# Link.net
KiCad netlist of a schematic drawn in EasyEDA Pro
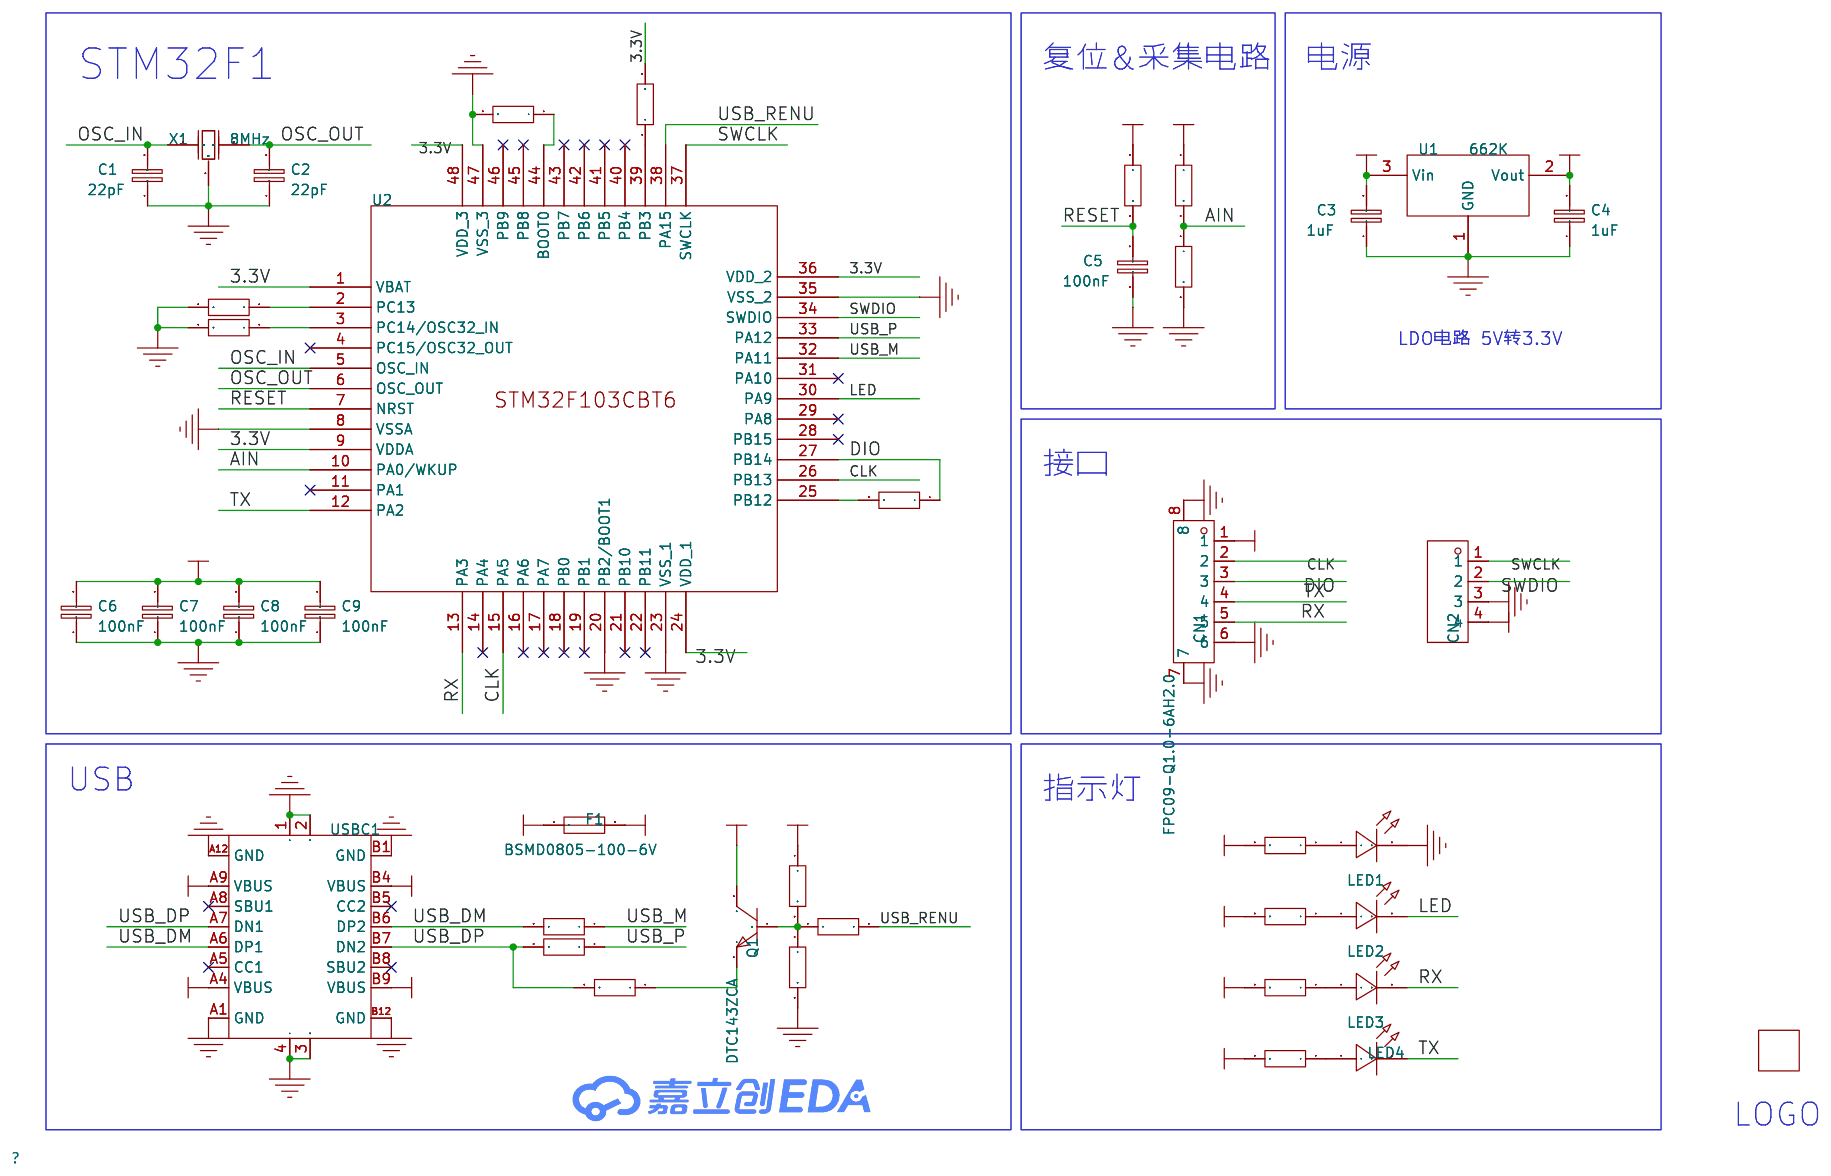
[diagram p0: schematic sheet]

(export (version "E")
  (design (tool "Eeschema 10.0.6"))
  (components
    (comp (ref "C1")
      (value "22pF")
      (fields
        (field (name "Manufacturer Part") "CL10C220JB8NNNC")
        (field (name "Manufacturer") "SAMSUNG(三星)")
      )
      (libsource (lib "easyedapro") (part "C0603"))
    )
    (comp (ref "C2")
      (value "22pF")
      (fields
        (field (name "Manufacturer Part") "CL10C220JB8NNNC")
        (field (name "Manufacturer") "SAMSUNG(三星)")
      )
      (libsource (lib "easyedapro") (part "C0603"))
    )
    (comp (ref "C3")
      (value "1uF")
      (fields
        (field (name "Manufacturer Part") "CL10A106KP8NNNC")
        (field (name "Manufacturer") "SAMSUNG(三星)")
      )
      (libsource (lib "easyedapro") (part "C0603"))
    )
    (comp (ref "C4")
      (value "1uF")
      (fields
        (field (name "Manufacturer Part") "CL10A106KP8NNNC")
        (field (name "Manufacturer") "SAMSUNG(三星)")
      )
      (libsource (lib "easyedapro") (part "C0603"))
    )
    (comp (ref "C5")
      (value "100nF")
      (fields
        (field (name "Manufacturer Part") "CC0603KRX7R9BB104")
        (field (name "Manufacturer") "YAGEO(国巨)")
      )
      (libsource (lib "easyedapro") (part "C0603"))
    )
    (comp (ref "C6")
      (value "100nF")
      (fields
        (field (name "Manufacturer Part") "CL10A106KP8NNNC")
        (field (name "Manufacturer") "SAMSUNG(三星)")
      )
      (libsource (lib "easyedapro") (part "C0603"))
    )
    (comp (ref "C7")
      (value "100nF")
      (fields
        (field (name "Manufacturer Part") "CL10A106KP8NNNC")
        (field (name "Manufacturer") "SAMSUNG(三星)")
      )
      (libsource (lib "easyedapro") (part "C0603"))
    )
    (comp (ref "C8")
      (value "100nF")
      (fields
        (field (name "Manufacturer Part") "CL10A106KP8NNNC")
        (field (name "Manufacturer") "SAMSUNG(三星)")
      )
      (libsource (lib "easyedapro") (part "C0603"))
    )
    (comp (ref "C9")
      (value "100nF")
      (fields
        (field (name "Manufacturer Part") "CL10A106KP8NNNC")
        (field (name "Manufacturer") "SAMSUNG(三星)")
      )
      (libsource (lib "easyedapro") (part "C0603"))
    )
    (comp (ref "CN1")
      (value "FPC09-Q1.0-6AH2.0")
      (fields (field (name "Manufacturer") "XYECONN(辛译)"))
      (libsource (lib "easyedapro") (part "WAFER-SH1.0-6PWB"))
    )
    (comp (ref "CN2")
      (value "X6511WRS-04H-C60D48")
      (footprint "easyedapro:HDR-SMD_4P-P2.54-H-M-W13.3-N")
      (fields (field (name "Manufacturer") "XKB Connection(中国星坤)"))
      (libsource (lib "easyedapro") (part "X6511WRS-04H- C60D48"))
    )
    (comp (ref "F1")
      (value "BSMD0805-100-6V")
      (fields (field (name "Manufacturer") "BHFUSE(佰宏)"))
      (libsource (lib "easyedapro") (part "F1206"))
    )
    (comp (ref "H1")
      (value "MoonGrt")
      (footprint "easyedapro:MoonGrt")
      (libsource (lib "easyedapro") (part "MoonGrt"))
    )
    (comp (ref "LED1")
      (value "LTST-C193TBKT-5A")
      (fields (field (name "Manufacturer") "LITEON(光宝)"))
      (libsource (lib "easyedapro") (part "LED0603B"))
    )
    (comp (ref "LED2")
      (value "LTST-C193TBKT-5A")
      (fields (field (name "Manufacturer") "LITEON(光宝)"))
      (libsource (lib "easyedapro") (part "LED0603B"))
    )
    (comp (ref "LED3")
      (value "LTST-C193TBKT-5A")
      (fields (field (name "Manufacturer") "LITEON(光宝)"))
      (libsource (lib "easyedapro") (part "LED0603B"))
    )
    (comp (ref "LED4")
      (value "LTST-C193TBKT-5A")
      (fields (field (name "Manufacturer") "LITEON(光宝)"))
      (libsource (lib "easyedapro") (part "LED0603B"))
    )
    (comp (ref "Q1")
      (value "DTC143ZCA")
      (fields (field (name "Manufacturer") "CJ(江苏长电/长晶)"))
      (libsource (lib "easyedapro") (part "MMBT3904_C7420353"))
    )
    (comp (ref "R1")
      (value "4.7kΩ")
      (fields
        (field (name "Manufacturer Part") "0603WAF4701T5E")
        (field (name "Manufacturer") "UNI-ROYAL(厚声)")
      )
      (libsource (lib "easyedapro") (part "R0603"))
    )
    (comp (ref "R2")
      (value "10kΩ")
      (fields
        (field (name "Manufacturer Part") "0603WAF1002T5E")
        (field (name "Manufacturer") "UNI-ROYAL(厚声)")
      )
      (libsource (lib "easyedapro") (part "R0603"))
    )
    (comp (ref "R3")
      (value "10kΩ")
      (fields
        (field (name "Manufacturer Part") "0603WAF1002T5E")
        (field (name "Manufacturer") "UNI-ROYAL(厚声)")
      )
      (libsource (lib "easyedapro") (part "R0603"))
    )
    (comp (ref "R4")
      (value "10kΩ")
      (fields
        (field (name "Manufacturer Part") "0603WAF1002T5E")
        (field (name "Manufacturer") "UNI-ROYAL(厚声)")
      )
      (libsource (lib "easyedapro") (part "R0603"))
    )
    (comp (ref "R5")
      (value "10kΩ")
      (fields
        (field (name "Manufacturer Part") "0603WAF1002T5E")
        (field (name "Manufacturer") "UNI-ROYAL(厚声)")
      )
      (libsource (lib "easyedapro") (part "R0603"))
    )
    (comp (ref "R6")
      (value "10kΩ")
      (fields
        (field (name "Manufacturer Part") "0603WAF1002T5E")
        (field (name "Manufacturer") "UNI-ROYAL(厚声)")
      )
      (libsource (lib "easyedapro") (part "R0603"))
    )
    (comp (ref "R7")
      (value "10kΩ")
      (fields
        (field (name "Manufacturer Part") "0603WAF1002T5E")
        (field (name "Manufacturer") "UNI-ROYAL(厚声)")
      )
      (libsource (lib "easyedapro") (part "R0603"))
    )
    (comp (ref "R8")
      (value "100Ω")
      (fields
        (field (name "Manufacturer Part") "0603WAF1000T5E")
        (field (name "Manufacturer") "UNI-ROYAL(厚声)")
      )
      (libsource (lib "easyedapro") (part "R0603"))
    )
    (comp (ref "R9")
      (value "1kΩ")
      (fields
        (field (name "Manufacturer Part") "0603WAF1001T5E")
        (field (name "Manufacturer") "UNI-ROYAL(厚声)")
      )
      (libsource (lib "easyedapro") (part "R0603"))
    )
    (comp (ref "R10")
      (value "10kΩ")
      (fields
        (field (name "Manufacturer Part") "0603WAF1002T5E")
        (field (name "Manufacturer") "UNI-ROYAL(厚声)")
      )
      (libsource (lib "easyedapro") (part "R0603"))
    )
    (comp (ref "R11")
      (value "22Ω")
      (fields
        (field (name "Manufacturer Part") "0603WAF220JT5E")
        (field (name "Manufacturer") "UNI-ROYAL(厚声)")
      )
      (libsource (lib "easyedapro") (part "R0603"))
    )
    (comp (ref "R12")
      (value "22Ω")
      (fields
        (field (name "Manufacturer Part") "0603WAF220JT5E")
        (field (name "Manufacturer") "UNI-ROYAL(厚声)")
      )
      (libsource (lib "easyedapro") (part "R0603"))
    )
    (comp (ref "R13")
      (value "100Ω")
      (fields
        (field (name "Manufacturer Part") "0603WAF1000T5E")
        (field (name "Manufacturer") "UNI-ROYAL(厚声)")
      )
      (libsource (lib "easyedapro") (part "R0603"))
    )
    (comp (ref "R14")
      (value "1kΩ")
      (fields
        (field (name "Manufacturer Part") "0603WAF1001T5E")
        (field (name "Manufacturer") "UNI-ROYAL(厚声)")
      )
      (libsource (lib "easyedapro") (part "R0603"))
    )
    (comp (ref "R15")
      (value "36kΩ")
      (fields
        (field (name "Manufacturer Part") "0603WAF3602T5E")
        (field (name "Manufacturer") "UNI-ROYAL(厚声)")
      )
      (libsource (lib "easyedapro") (part "R0603"))
    )
    (comp (ref "R16")
      (value "1.5kΩ")
      (fields
        (field (name "Manufacturer Part") "0603WAF1501T5E")
        (field (name "Manufacturer") "UNI-ROYAL(厚声)")
      )
      (libsource (lib "easyedapro") (part "R0603"))
    )
    (comp (ref "R17")
      (value "1kΩ")
      (fields
        (field (name "Manufacturer Part") "0603WAF1001T5E")
        (field (name "Manufacturer") "UNI-ROYAL(厚声)")
      )
      (libsource (lib "easyedapro") (part "R0603"))
    )
    (comp (ref "R18")
      (value "1kΩ")
      (fields
        (field (name "Manufacturer Part") "0603WAF1001T5E")
        (field (name "Manufacturer") "UNI-ROYAL(厚声)")
      )
      (libsource (lib "easyedapro") (part "R0603"))
    )
    (comp (ref "U1")
      (value "662K")
      (footprint "easyedapro:SOT-23-3_L2.9-W1.3-P1.90-LS2.4-BR")
      (fields (field (name "Manufacturer") "HXY MOSFET(华轩阳电子)"))
      (libsource (lib "easyedapro") (part "LM317"))
    )
    (comp (ref "U2")
      (value "STM32F103CBT6")
      (footprint "easyedapro:LQFP-48_L7.0-W7.0-P0.50-LS9.0-BL")
      (fields (field (name "Manufacturer") "ST(意法半导体)"))
      (libsource (lib "easyedapro") (part "STM32F103C8T6"))
    )
    (comp (ref "USBC1")
      (value "TYPE-C-31-M-12")
      (footprint "easyedapro:USB-C_SMD-TYPE-C-31-M-12")
      (description "连接器类型:Type-C;标准:-;公母:母;安装方式:-;触点数量:16P;端口数量:1;额定电流 - 电源:5A;工作温度范围:-;")
      (fields (field (name "Manufacturer") "韩国韩荣"))
      (libsource (lib "easyedapro") (part "TYPE-C-31-M-12"))
    )
    (comp (ref "X1")
      (value "8MHz")
      (footprint "easyedapro:OSC-SMD_3P-L3.2-W1.3-P1.20-L")
      (fields
        (field (name "Manufacturer Part") "CSTNE8M00GH5C000R0")
        (field (name "Manufacturer") "muRata(村田)")
      )
      (libsource (lib "easyedapro") (part "CSTNE8M00GH5C000R0"))
    )
  )
  (nets
    (net (code "1") (name "/AIN") (class "Default")
      (node (ref "R4") (pin "2") (pinfunction "2_2") (pintype "unspecified"))
      (node (ref "R5") (pin "1") (pinfunction "1_1") (pintype "unspecified"))
      (node (ref "U2") (pin "10") (pinfunction "PA0/WKUP_10") (pintype "unspecified"))
    )
    (net (code "2") (name "/CLK") (class "Default")
      (node (ref "CN1") (pin "2") (pinfunction "2_2") (pintype "unspecified"))
      (node (ref "U2") (pin "15") (pinfunction "PA5_15") (pintype "unspecified"))
      (node (ref "U2") (pin "26") (pinfunction "PB13_26") (pintype "unspecified"))
    )
    (net (code "3") (name "/DIO") (class "Default")
      (node (ref "CN1") (pin "3") (pinfunction "3_3") (pintype "unspecified"))
      (node (ref "R8") (pin "1") (pinfunction "1_1") (pintype "unspecified"))
      (node (ref "U2") (pin "27") (pinfunction "PB14_27") (pintype "unspecified"))
    )
    (net (code "4") (name "/LED") (class "Default")
      (node (ref "LED2") (pin "2") (pinfunction "2_2") (pintype "unspecified"))
      (node (ref "U2") (pin "30") (pinfunction "PA9_30") (pintype "unspecified"))
    )
    (net (code "5") (name "/OSC_IN") (class "Default")
      (node (ref "C1") (pin "2") (pinfunction "2_2") (pintype "unspecified"))
      (node (ref "U2") (pin "5") (pinfunction "OSC_IN_5") (pintype "unspecified"))
      (node (ref "X1") (pin "3") (pinfunction "OSC2_3") (pintype "input"))
    )
    (net (code "6") (name "/OSC_OUT") (class "Default")
      (node (ref "C2") (pin "2") (pinfunction "2_2") (pintype "unspecified"))
      (node (ref "U2") (pin "6") (pinfunction "OSC_OUT_6") (pintype "unspecified"))
      (node (ref "X1") (pin "1") (pinfunction "OSC1_1") (pintype "input"))
    )
    (net (code "7") (name "/RESET") (class "Default")
      (node (ref "C5") (pin "2") (pinfunction "2_2") (pintype "unspecified"))
      (node (ref "R3") (pin "2") (pinfunction "2_2") (pintype "unspecified"))
      (node (ref "U2") (pin "7") (pinfunction "NRST_7") (pintype "unspecified"))
    )
    (net (code "8") (name "/RX") (class "Default")
      (node (ref "CN1") (pin "5") (pinfunction "5_5") (pintype "unspecified"))
      (node (ref "LED3") (pin "2") (pinfunction "2_2") (pintype "unspecified"))
      (node (ref "U2") (pin "13") (pinfunction "PA3_13") (pintype "unspecified"))
    )
    (net (code "9") (name "/SWCLK") (class "Default")
      (node (ref "CN2") (pin "1") (pinfunction "1_1") (pintype "unspecified"))
      (node (ref "U2") (pin "37") (pinfunction "SWCLK_37") (pintype "unspecified"))
    )
    (net (code "10") (name "/SWDIO") (class "Default")
      (node (ref "CN2") (pin "2") (pinfunction "2_2") (pintype "unspecified"))
      (node (ref "U2") (pin "34") (pinfunction "SWDIO_34") (pintype "unspecified"))
    )
    (net (code "11") (name "/TX") (class "Default")
      (node (ref "CN1") (pin "4") (pinfunction "4_4") (pintype "unspecified"))
      (node (ref "LED4") (pin "2") (pinfunction "2_2") (pintype "unspecified"))
      (node (ref "U2") (pin "12") (pinfunction "PA2_12") (pintype "unspecified"))
    )
    (net (code "12") (name "/USB_DM") (class "Default")
      (node (ref "R11") (pin "2") (pinfunction "2_2") (pintype "unspecified"))
      (node (ref "USBC1") (pin "A6") (pinfunction "DP1_A6") (pintype "unspecified"))
      (node (ref "USBC1") (pin "B6") (pinfunction "DP2_B6") (pintype "unspecified"))
    )
    (net (code "13") (name "/USB_DP") (class "Default")
      (node (ref "R12") (pin "2") (pinfunction "2_2") (pintype "unspecified"))
      (node (ref "R16") (pin "2") (pinfunction "2_2") (pintype "unspecified"))
      (node (ref "USBC1") (pin "A7") (pinfunction "DN1_A7") (pintype "unspecified"))
      (node (ref "USBC1") (pin "B7") (pinfunction "DN2_B7") (pintype "unspecified"))
    )
    (net (code "14") (name "/USB_M") (class "Default")
      (node (ref "R11") (pin "1") (pinfunction "1_1") (pintype "unspecified"))
      (node (ref "U2") (pin "32") (pinfunction "PA11_32") (pintype "unspecified"))
    )
    (net (code "15") (name "/USB_P") (class "Default")
      (node (ref "R12") (pin "1") (pinfunction "1_1") (pintype "unspecified"))
      (node (ref "U2") (pin "33") (pinfunction "PA12_33") (pintype "unspecified"))
    )
    (net (code "16") (name "/USB_RENU") (class "Default")
      (node (ref "R13") (pin "2") (pinfunction "2_2") (pintype "unspecified"))
      (node (ref "U2") (pin "38") (pinfunction "PA15_38") (pintype "unspecified"))
    )
    (net (code "17") (name "3.3V") (class "Default")
      (node (ref "C4") (pin "2") (pinfunction "2_2") (pintype "unspecified"))
      (node (ref "C6") (pin "2") (pinfunction "2_2") (pintype "unspecified"))
      (node (ref "C7") (pin "2") (pinfunction "2_2") (pintype "unspecified"))
      (node (ref "C8") (pin "2") (pinfunction "2_2") (pintype "unspecified"))
      (node (ref "C9") (pin "2") (pinfunction "2_2") (pintype "unspecified"))
      (node (ref "CN1") (pin "1") (pinfunction "1_1") (pintype "unspecified"))
      (node (ref "CN2") (pin "4") (pinfunction "4_4") (pintype "unspecified"))
      (node (ref "Q1") (pin "3") (pinfunction "C_3") (pintype "unspecified"))
      (node (ref "R1") (pin "2") (pinfunction "2_2") (pintype "unspecified"))
      (node (ref "R14") (pin "2") (pinfunction "2_2") (pintype "unspecified"))
      (node (ref "R17") (pin "2") (pinfunction "2_2") (pintype "unspecified"))
      (node (ref "R18") (pin "2") (pinfunction "2_2") (pintype "unspecified"))
      (node (ref "R3") (pin "1") (pinfunction "1_1") (pintype "unspecified"))
      (node (ref "R4") (pin "1") (pinfunction "1_1") (pintype "unspecified"))
      (node (ref "R9") (pin "2") (pinfunction "2_2") (pintype "unspecified"))
      (node (ref "U1") (pin "2") (pinfunction "Vout_2") (pintype "unspecified"))
      (node (ref "U2") (pin "1") (pinfunction "VBAT_1") (pintype "unspecified"))
      (node (ref "U2") (pin "24") (pinfunction "VDD_1_24") (pintype "unspecified"))
      (node (ref "U2") (pin "36") (pinfunction "VDD_2_36") (pintype "unspecified"))
      (node (ref "U2") (pin "48") (pinfunction "VDD_3_48") (pintype "unspecified"))
      (node (ref "U2") (pin "9") (pinfunction "VDDA_9") (pintype "unspecified"))
    )
    (net (code "18") (name "5V") (class "Default")
      (node (ref "C3") (pin "2") (pinfunction "2_2") (pintype "unspecified"))
      (node (ref "F1") (pin "2") (pinfunction "2_2") (pintype "unspecified"))
      (node (ref "R10") (pin "1") (pinfunction "1_1") (pintype "unspecified"))
      (node (ref "U1") (pin "3") (pinfunction "Vin_3") (pintype "unspecified"))
    )
    (net (code "19") (name "GND") (class "Default")
      (node (ref "C1") (pin "1") (pinfunction "1_1") (pintype "unspecified"))
      (node (ref "C2") (pin "1") (pinfunction "1_1") (pintype "unspecified"))
      (node (ref "C3") (pin "1") (pinfunction "1_1") (pintype "unspecified"))
      (node (ref "C4") (pin "1") (pinfunction "1_1") (pintype "unspecified"))
      (node (ref "C5") (pin "1") (pinfunction "1_1") (pintype "unspecified"))
      (node (ref "C6") (pin "1") (pinfunction "1_1") (pintype "unspecified"))
      (node (ref "C7") (pin "1") (pinfunction "1_1") (pintype "unspecified"))
      (node (ref "C8") (pin "1") (pinfunction "1_1") (pintype "unspecified"))
      (node (ref "C9") (pin "1") (pinfunction "1_1") (pintype "unspecified"))
      (node (ref "CN1") (pin "6") (pinfunction "6_6") (pintype "unspecified"))
      (node (ref "CN1") (pin "7") (pinfunction "7_7") (pintype "unspecified"))
      (node (ref "CN1") (pin "8") (pinfunction "8_8") (pintype "unspecified"))
      (node (ref "CN2") (pin "3") (pinfunction "3_3") (pintype "unspecified"))
      (node (ref "LED1") (pin "2") (pinfunction "2_2") (pintype "unspecified"))
      (node (ref "R15") (pin "2") (pinfunction "2_2") (pintype "unspecified"))
      (node (ref "R2") (pin "2") (pinfunction "2_2") (pintype "unspecified"))
      (node (ref "R5") (pin "2") (pinfunction "2_2") (pintype "unspecified"))
      (node (ref "R6") (pin "2") (pinfunction "2_2") (pintype "unspecified"))
      (node (ref "R7") (pin "2") (pinfunction "2_2") (pintype "unspecified"))
      (node (ref "U1") (pin "1") (pinfunction "GND_1") (pintype "unspecified"))
      (node (ref "U2") (pin "20") (pinfunction "PB2/BOOT1_20") (pintype "unspecified"))
      (node (ref "U2") (pin "23") (pinfunction "VSS_1_23") (pintype "unspecified"))
      (node (ref "U2") (pin "35") (pinfunction "VSS_2_35") (pintype "unspecified"))
      (node (ref "U2") (pin "47") (pinfunction "VSS_3_47") (pintype "unspecified"))
      (node (ref "U2") (pin "8") (pinfunction "VSSA_8") (pintype "unspecified"))
      (node (ref "USBC1") (pin "1") (pinfunction "1_1") (pintype "unspecified"))
      (node (ref "USBC1") (pin "2") (pinfunction "2_2") (pintype "unspecified"))
      (node (ref "USBC1") (pin "3") (pinfunction "3_3") (pintype "unspecified"))
      (node (ref "USBC1") (pin "4") (pinfunction "4_4") (pintype "unspecified"))
      (node (ref "USBC1") (pin "A1") (pinfunction "GND_A1") (pintype "unspecified"))
      (node (ref "USBC1") (pin "A12") (pinfunction "GND_A12") (pintype "unspecified"))
      (node (ref "USBC1") (pin "B1") (pinfunction "GND_B1") (pintype "unspecified"))
      (node (ref "USBC1") (pin "B12") (pinfunction "GND_B12") (pintype "unspecified"))
      (node (ref "X1") (pin "2") (pinfunction "GND_2") (pintype "input"))
    )
    (net (code "20") (name "Net-(LED1-Pad1)") (class "Default")
      (node (ref "LED1") (pin "1") (pinfunction "1_1") (pintype "unspecified"))
      (node (ref "R9") (pin "1") (pinfunction "1_1") (pintype "unspecified"))
    )
    (net (code "21") (name "Net-(LED2-Pad1)") (class "Default")
      (node (ref "LED2") (pin "1") (pinfunction "1_1") (pintype "unspecified"))
      (node (ref "R14") (pin "1") (pinfunction "1_1") (pintype "unspecified"))
    )
    (net (code "22") (name "Net-(LED3-Pad1)") (class "Default")
      (node (ref "LED3") (pin "1") (pinfunction "1_1") (pintype "unspecified"))
      (node (ref "R17") (pin "1") (pinfunction "1_1") (pintype "unspecified"))
    )
    (net (code "23") (name "Net-(LED4-Pad1)") (class "Default")
      (node (ref "LED4") (pin "1") (pinfunction "1_1") (pintype "unspecified"))
      (node (ref "R18") (pin "1") (pinfunction "1_1") (pintype "unspecified"))
    )
    (net (code "24") (name "Net-(Q1-B)") (class "Default")
      (node (ref "Q1") (pin "1") (pinfunction "B_1") (pintype "unspecified"))
      (node (ref "R10") (pin "2") (pinfunction "2_2") (pintype "unspecified"))
      (node (ref "R13") (pin "1") (pinfunction "1_1") (pintype "unspecified"))
      (node (ref "R15") (pin "1") (pinfunction "1_1") (pintype "unspecified"))
    )
    (net (code "25") (name "Net-(Q1-E)") (class "Default")
      (node (ref "Q1") (pin "2") (pinfunction "E_2") (pintype "unspecified"))
      (node (ref "R16") (pin "1") (pinfunction "1_1") (pintype "unspecified"))
    )
    (net (code "26") (name "Net-(U2-BOOT0)") (class "Default")
      (node (ref "R2") (pin "1") (pinfunction "1_1") (pintype "unspecified"))
      (node (ref "U2") (pin "44") (pinfunction "BOOT0_44") (pintype "unspecified"))
    )
    (net (code "27") (name "Net-(U2-PB3)") (class "Default")
      (node (ref "R1") (pin "1") (pinfunction "1_1") (pintype "unspecified"))
      (node (ref "U2") (pin "39") (pinfunction "PB3_39") (pintype "unspecified"))
    )
    (net (code "28") (name "Net-(U2-PB12)") (class "Default")
      (node (ref "R8") (pin "2") (pinfunction "2_2") (pintype "unspecified"))
      (node (ref "U2") (pin "25") (pinfunction "PB12_25") (pintype "unspecified"))
    )
    (net (code "29") (name "Net-(U2-PC13)") (class "Default")
      (node (ref "R6") (pin "1") (pinfunction "1_1") (pintype "unspecified"))
      (node (ref "U2") (pin "2") (pinfunction "PC13_2") (pintype "unspecified"))
    )
    (net (code "30") (name "Net-(U2-PC14{slash}OSC32_IN)") (class "Default")
      (node (ref "R7") (pin "1") (pinfunction "1_1") (pintype "unspecified"))
      (node (ref "U2") (pin "3") (pinfunction "PC14/OSC32_IN_3") (pintype "unspecified"))
    )
    (net (code "31") (name "VBUS") (class "Default")
      (node (ref "F1") (pin "1") (pinfunction "1_1") (pintype "unspecified"))
      (node (ref "USBC1") (pin "A4") (pinfunction "VBUS_A4") (pintype "unspecified"))
      (node (ref "USBC1") (pin "A9") (pinfunction "VBUS_A9") (pintype "unspecified"))
      (node (ref "USBC1") (pin "B4") (pinfunction "VBUS_B4") (pintype "unspecified"))
      (node (ref "USBC1") (pin "B9") (pinfunction "VBUS_B9") (pintype "unspecified"))
    )
    (net (code "32") (name "unconnected-(U2-PA1-Pad11)") (class "Default")
      (node (ref "U2") (pin "11") (pinfunction "PA1_11") (pintype "unspecified+no_connect"))
    )
    (net (code "33") (name "unconnected-(U2-PA4-Pad14)") (class "Default")
      (node (ref "U2") (pin "14") (pinfunction "PA4_14") (pintype "unspecified+no_connect"))
    )
    (net (code "34") (name "unconnected-(U2-PA6-Pad16)") (class "Default")
      (node (ref "U2") (pin "16") (pinfunction "PA6_16") (pintype "unspecified+no_connect"))
    )
    (net (code "35") (name "unconnected-(U2-PA7-Pad17)") (class "Default")
      (node (ref "U2") (pin "17") (pinfunction "PA7_17") (pintype "unspecified+no_connect"))
    )
    (net (code "36") (name "unconnected-(U2-PA8-Pad29)") (class "Default")
      (node (ref "U2") (pin "29") (pinfunction "PA8_29") (pintype "unspecified+no_connect"))
    )
    (net (code "37") (name "unconnected-(U2-PA10-Pad31)") (class "Default")
      (node (ref "U2") (pin "31") (pinfunction "PA10_31") (pintype "unspecified+no_connect"))
    )
    (net (code "38") (name "unconnected-(U2-PB0-Pad18)") (class "Default")
      (node (ref "U2") (pin "18") (pinfunction "PB0_18") (pintype "unspecified+no_connect"))
    )
    (net (code "39") (name "unconnected-(U2-PB1-Pad19)") (class "Default")
      (node (ref "U2") (pin "19") (pinfunction "PB1_19") (pintype "unspecified+no_connect"))
    )
    (net (code "40") (name "unconnected-(U2-PB4-Pad40)") (class "Default")
      (node (ref "U2") (pin "40") (pinfunction "PB4_40") (pintype "unspecified+no_connect"))
    )
    (net (code "41") (name "unconnected-(U2-PB5-Pad41)") (class "Default")
      (node (ref "U2") (pin "41") (pinfunction "PB5_41") (pintype "unspecified+no_connect"))
    )
    (net (code "42") (name "unconnected-(U2-PB6-Pad42)") (class "Default")
      (node (ref "U2") (pin "42") (pinfunction "PB6_42") (pintype "unspecified+no_connect"))
    )
    (net (code "43") (name "unconnected-(U2-PB7-Pad43)") (class "Default")
      (node (ref "U2") (pin "43") (pinfunction "PB7_43") (pintype "unspecified+no_connect"))
    )
    (net (code "44") (name "unconnected-(U2-PB8-Pad45)") (class "Default")
      (node (ref "U2") (pin "45") (pinfunction "PB8_45") (pintype "unspecified+no_connect"))
    )
    (net (code "45") (name "unconnected-(U2-PB9-Pad46)") (class "Default")
      (node (ref "U2") (pin "46") (pinfunction "PB9_46") (pintype "unspecified+no_connect"))
    )
    (net (code "46") (name "unconnected-(U2-PB10-Pad21)") (class "Default")
      (node (ref "U2") (pin "21") (pinfunction "PB10_21") (pintype "unspecified+no_connect"))
    )
    (net (code "47") (name "unconnected-(U2-PB11-Pad22)") (class "Default")
      (node (ref "U2") (pin "22") (pinfunction "PB11_22") (pintype "unspecified+no_connect"))
    )
    (net (code "48") (name "unconnected-(U2-PB15-Pad28)") (class "Default")
      (node (ref "U2") (pin "28") (pinfunction "PB15_28") (pintype "unspecified+no_connect"))
    )
    (net (code "49") (name "unconnected-(U2-PC15{slash}OSC32_OUT-Pad4)") (class "Default")
      (node (ref "U2") (pin "4") (pinfunction "PC15/OSC32_OUT_4") (pintype "unspecified+no_connect"))
    )
    (net (code "50") (name "unconnected-(USBC1-CC1-PadA5)") (class "Default")
      (node (ref "USBC1") (pin "A5") (pinfunction "CC1_A5") (pintype "unspecified+no_connect"))
    )
    (net (code "51") (name "unconnected-(USBC1-CC2-PadB5)") (class "Default")
      (node (ref "USBC1") (pin "B5") (pinfunction "CC2_B5") (pintype "unspecified+no_connect"))
    )
    (net (code "52") (name "unconnected-(USBC1-SBU1-PadA8)") (class "Default")
      (node (ref "USBC1") (pin "A8") (pinfunction "SBU1_A8") (pintype "unspecified+no_connect"))
    )
    (net (code "53") (name "unconnected-(USBC1-SBU2-PadB8)") (class "Default")
      (node (ref "USBC1") (pin "B8") (pinfunction "SBU2_B8") (pintype "unspecified+no_connect"))
    )
  )
)
